# PAGE2-CPU.net
KiCad netlist of a schematic drawn in Altium Designer
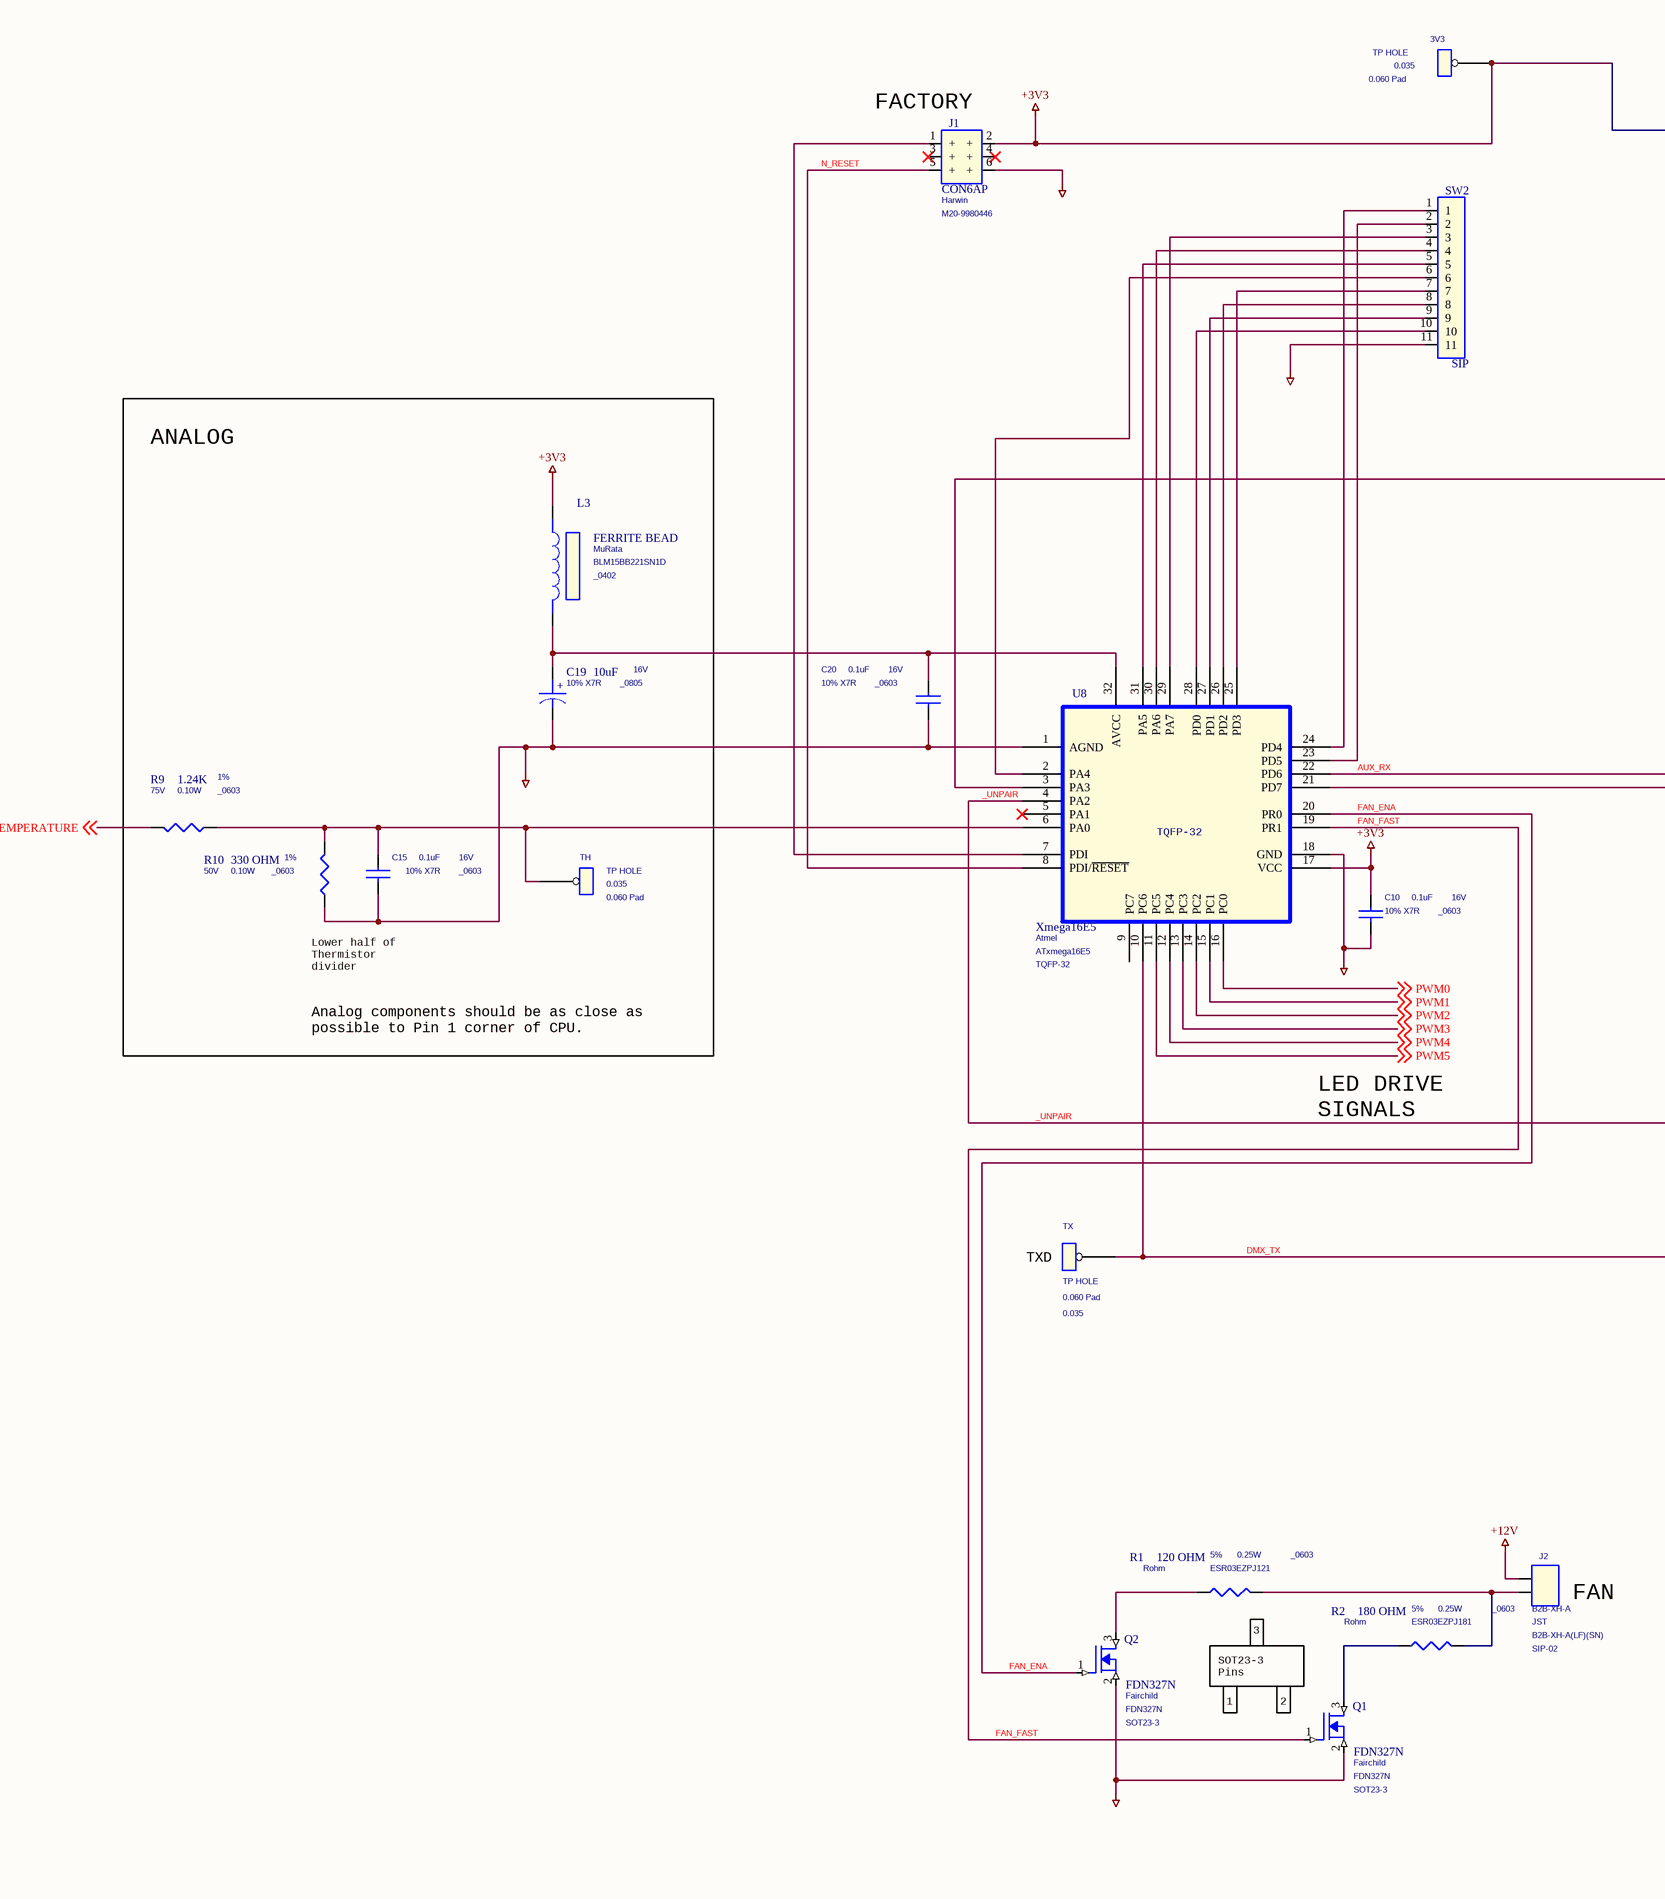
[diagram p0: PAGE2-CPU.SchDoc, left]
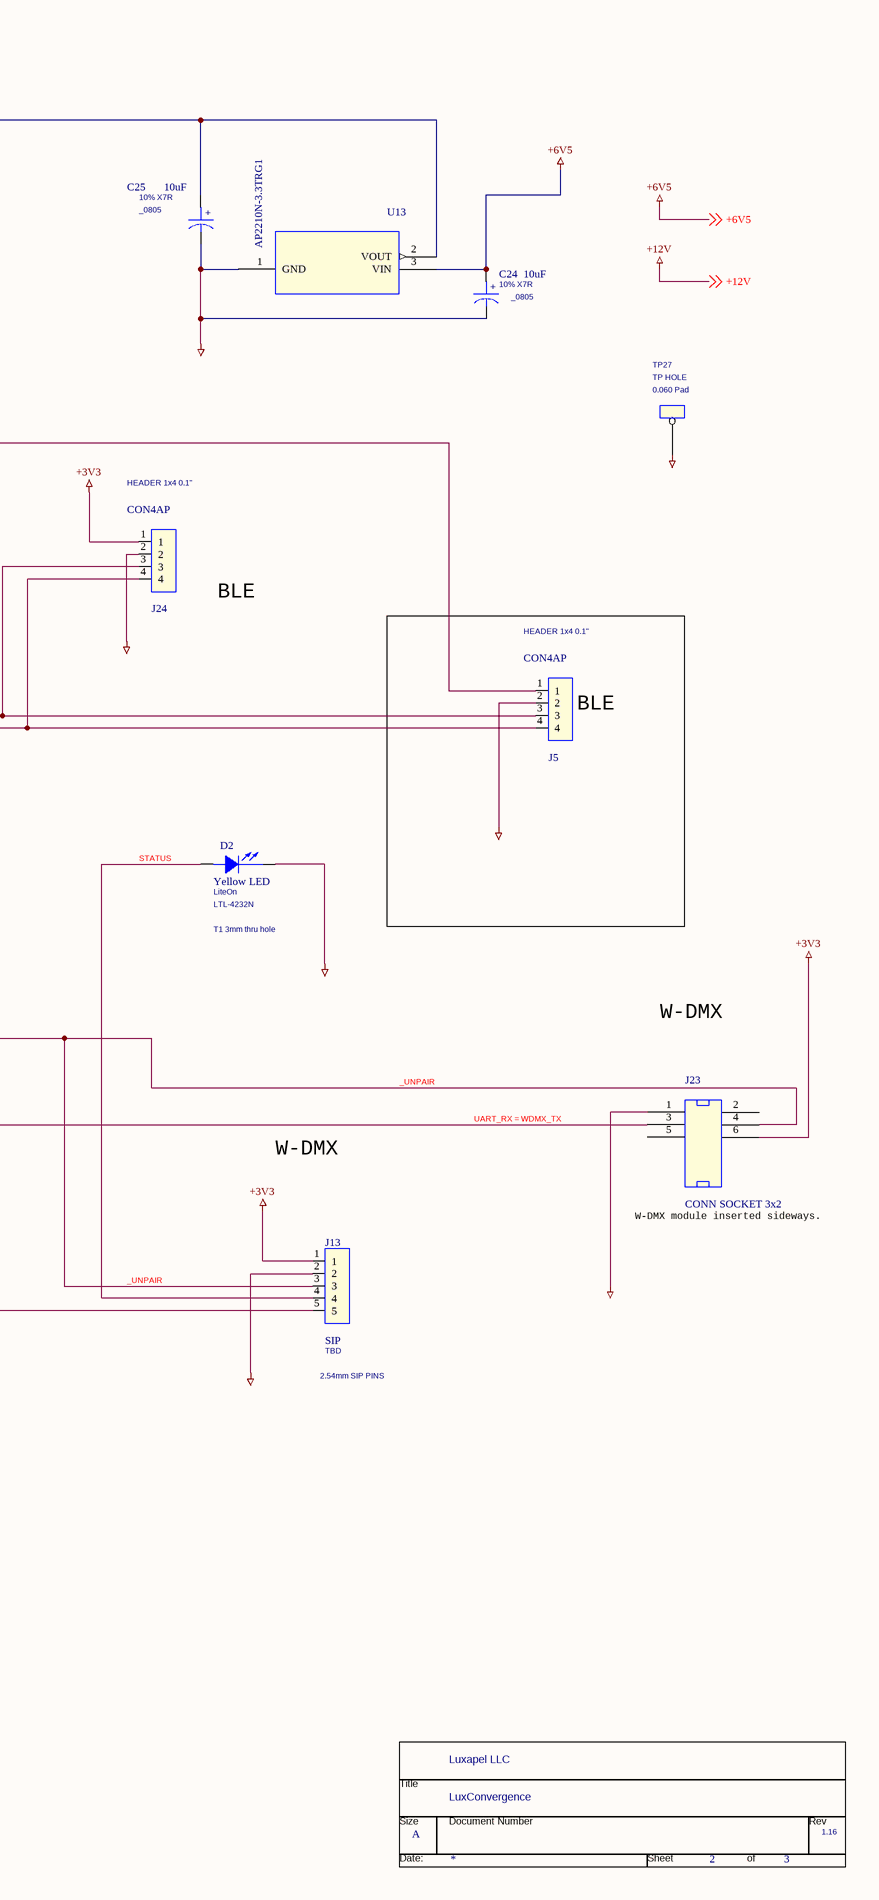
[diagram p1: PAGE2-CPU.SchDoc, right]

(export (version "E")
  (design (tool "Eeschema 10.0.6"))
  (components
    (comp (ref "3V3")
      (value "TP HOLE")
      (footprint "0.035")
      (fields (field (name "NOTES") "0.060 Pad") (field (name "PCB FOOTPRINT") "0.035"))
      (libsource (lib "*") (part "TEST POINT_1"))
    )
    (comp (ref "C10")
      (value "0.1uF")
      (footprint "_0603")
      (fields
        (field (name "PCB FOOTPRINT") "_0603")
        (field (name "VOLTAGE") "16V")
        (field (name "PRECISION") "10% X7R")
        (field (name "MFG") "AVX")
      )
      (libsource (lib "*") (part "CAPACITOR NON-POL"))
    )
    (comp (ref "C15")
      (value "0.1uF")
      (footprint "_0603")
      (fields
        (field (name "PCB FOOTPRINT") "_0603")
        (field (name "MFG") "AVX")
        (field (name "PRECISION") "10% X7R")
        (field (name "VOLTAGE") "16V")
      )
      (libsource (lib "*") (part "CAPACITOR NON-POL"))
    )
    (comp (ref "C19")
      (value "10uF")
      (footprint "_0805")
      (fields
        (field (name "PCB FOOTPRINT") "_0805")
        (field (name "MFG") "Samsung")
        (field (name "VOLTAGE") "16V")
        (field (name "PRECISION") "10% X7R")
      )
      (libsource (lib "*") (part "CAPACITOR POL/SM"))
    )
    (comp (ref "C20")
      (value "0.1uF")
      (footprint "_0603")
      (fields
        (field (name "MFG") "AVX")
        (field (name "PRECISION") "10% X7R")
        (field (name "VOLTAGE") "16V")
        (field (name "PCB FOOTPRINT") "_0603")
      )
      (libsource (lib "*") (part "CAPACITOR NON-POL"))
    )
    (comp (ref "C24")
      (value "10uF")
      (footprint "_0805")
      (fields
        (field (name "PRECISION") "10% X7R")
        (field (name "VOLTAGE") "16V")
        (field (name "MFG") "Samsung")
        (field (name "PCB FOOTPRINT") "_0805")
      )
      (libsource (lib "*") (part "CAPACITOR POL/SM"))
    )
    (comp (ref "C25")
      (value "10uF")
      (footprint "_0805")
      (fields
        (field (name "MFG") "Samsung")
        (field (name "VOLTAGE") "16V")
        (field (name "PRECISION") "10% X7R")
        (field (name "PCB FOOTPRINT") "_0805")
      )
      (libsource (lib "*") (part "CAPACITOR POL/SM"))
    )
    (comp (ref "D2")
      (value "Yellow LED")
      (footprint "T1 3mm thru hole")
      (fields
        (field (name "MFG") "LiteOn")
        (field (name "P/N") "LTL-4232N")
        (field (name "PCB FOOTPRINT") "T1 3mm thru hole")
      )
      (libsource (lib "*") (part "LED"))
    )
    (comp (ref "J1")
      (value "CON6AP")
      (footprint "2x4")
      (fields (field (name "MFG") "Harwin") (field (name "P/N") "M20-9980446"))
      (libsource (lib "*") (part "CON8AP_0"))
    )
    (comp (ref "J2")
      (value "B2B-XH-A")
      (footprint "SIP-02")
      (fields
        (field (name "P/N") "B2B-XH-A(LF)(SN)")
        (field (name "MFG") "JST")
        (field (name "PCB FOOTPRINT") "SIP-02")
      )
      (libsource (lib "*") (part "CON2"))
    )
    (comp (ref "J5")
      (value "CON4AP")
      (footprint "HEADER 1x4 0.1\"")
      (fields (field (name "PCB FOOTPRINT") "HEADER 1x4 0.1\""))
      (libsource (lib "*") (part "CON4AP_5"))
    )
    (comp (ref "J13")
      (value "SIP")
      (footprint "SIP-4")
      (fields (field (name "MFG") "TBD") (field (name "P/N") "2.54mm SIP PINS"))
      (libsource (lib "*") (part "CON4_9"))
    )
    (comp (ref "J23")
      (value "CONN SOCKET 3x2")
      (footprint "2X3")
      (libsource (lib "*") (part "CONN SOCKET 6x2_0"))
    )
    (comp (ref "J24")
      (value "CON4AP")
      (footprint "SIP-4PA")
      (fields (field (name "PCB FOOTPRINT") "HEADER 1x4 0.1\""))
      (libsource (lib "*") (part "CON4AP_5"))
    )
    (comp (ref "L3")
      (value "FERRITE BEAD")
      (footprint "_0402")
      (fields
        (field (name "MFG") "MuRata")
        (field (name "P/N") "BLM15BB221SN1D")
        (field (name "PCB FOOTPRINT") "_0402")
      )
      (libsource (lib "*") (part "INDUCTOR FERRITE/SM"))
    )
    (comp (ref "Q1")
      (value "FDN327N")
      (footprint "SOT23-3")
      (fields
        (field (name "P/N") "FDN327N")
        (field (name "MFG") "Fairchild")
        (field (name "VOLTAGE") "20V")
        (field (name "POWER") "2A")
        (field (name "PCB FOOTPRINT") "SOT23-3")
      )
      (libsource (lib "*") (part "N DGS_0"))
    )
    (comp (ref "Q2")
      (value "FDN327N")
      (footprint "SOT23-3")
      (fields
        (field (name "MFG") "Fairchild")
        (field (name "P/N") "FDN327N")
        (field (name "VOLTAGE") "20V")
        (field (name "POWER") "2A")
        (field (name "PCB FOOTPRINT") "SOT23-3")
      )
      (libsource (lib "*") (part "N DGS_0"))
    )
    (comp (ref "R1")
      (value "120 OHM")
      (footprint "_0603")
      (fields
        (field (name "VOLTAGE") "50V")
        (field (name "PRECISION") "5%")
        (field (name "POWER") "0.25W")
        (field (name "P/N") "ESR03EZPJ121")
        (field (name "MFG") "Rohm")
        (field (name "PCB FOOTPRINT") "_0603")
      )
      (libsource (lib "*") (part "RESISTOR/SM"))
    )
    (comp (ref "R2")
      (value "180 OHM")
      (footprint "_0603")
      (fields
        (field (name "VOLTAGE") "50V")
        (field (name "PRECISION") "5%")
        (field (name "POWER") "0.25W")
        (field (name "P/N") "ESR03EZPJ181")
        (field (name "MFG") "Rohm")
        (field (name "PCB FOOTPRINT") "_0603")
      )
      (libsource (lib "*") (part "RESISTOR/SM"))
    )
    (comp (ref "R9")
      (value "1.24K")
      (footprint "_0603")
      (fields
        (field (name "PCB FOOTPRINT") "_0603")
        (field (name "POWER") "0.10W")
        (field (name "VOLTAGE") "75V")
        (field (name "MFG") "Vishay")
        (field (name "PRECISION") "1%")
      )
      (libsource (lib "*") (part "RESISTOR/SM"))
    )
    (comp (ref "R10")
      (value "330 OHM")
      (footprint "_0603")
      (fields
        (field (name "PCB FOOTPRINT") "_0603")
        (field (name "VOLTAGE") "50V")
        (field (name "PRECISION") "1%")
        (field (name "POWER") "0.10W")
        (field (name "MFG") "Stackpole")
      )
      (libsource (lib "*") (part "RESISTOR/SM"))
    )
    (comp (ref "SW2")
      (value "SIP")
      (footprint "SIP-4")
      (fields (field (name "MFG") "TBD"))
      (libsource (lib "*") (part "CON4_10"))
    )
    (comp (ref "TH")
      (value "TP HOLE")
      (footprint "0.035")
      (fields (field (name "NOTES") "0.060 Pad") (field (name "PCB FOOTPRINT") "0.035"))
      (libsource (lib "") (part "TEST POINT_1_2"))
    )
    (comp (ref "TP27")
      (value "TP HOLE")
      (footprint "0.035")
      (fields (field (name "NOTES") "0.060 Pad"))
      (libsource (lib "") (part "TEST POINT_1_1"))
    )
    (comp (ref "TX")
      (value "TP HOLE")
      (footprint "0.035")
      (fields (field (name "PCB FOOTPRINT") "0.035") (field (name "NOTES") "0.060 Pad"))
      (libsource (lib "*") (part "TEST POINT_1"))
    )
    (comp (ref "U8")
      (value "Xmega16E5")
      (footprint "TQFP-32")
      (fields
        (field (name "P/N") "ATxmega16E5")
        (field (name "MFG") "Atmel")
        (field (name "PCB FOOTPRINT") "TQFP-32")
      )
      (libsource (lib "*") (part "Xmega8E5"))
    )
    (comp (ref "U13")
      (value "AP2210N-3.3TRG1")
      (footprint "FP-SOT23-IPC_A")
      (fields (field (name "COPYRIGHT") "Copyright (C) 2018 Accelerated Designs. All rights reserved"))
      (libsource (lib "*") (part "AP2210N-3P3TRG1"))
    )
  )
  (nets
    (net (code "1") (name "+3V3") (class "Default")
      (node (ref "3V3") (pin "1") (pinfunction "1_1") (pintype "passive"))
      (node (ref "C10") (pin "1") (pinfunction "1_1") (pintype "passive"))
      (node (ref "C25") (pin "1") (pinfunction "1_1") (pintype "passive"))
      (node (ref "J1") (pin "2") (pinfunction "+_2") (pintype "passive"))
      (node (ref "J13") (pin "1") (pinfunction "1_1") (pintype "passive"))
      (node (ref "J23") (pin "6") (pinfunction "9_6") (pintype "passive"))
      (node (ref "J24") (pin "1") (pinfunction "1_1") (pintype "passive"))
      (node (ref "L3") (pin "2") (pinfunction "2_2") (pintype "passive"))
      (node (ref "U13") (pin "2") (pinfunction "VOUT_2") (pintype "output"))
      (node (ref "U8") (pin "17") (pinfunction "VCC_17") (pintype "power_in"))
    )
    (net (code "2") (name "+6V5") (class "Default")
      (node (ref "C24") (pin "1") (pinfunction "1_1") (pintype "passive"))
      (node (ref "U13") (pin "3") (pinfunction "VIN_3") (pintype "passive"))
    )
    (net (code "3") (name "+12V") (class "Default")
      (node (ref "J2") (pin "1") (pinfunction "1_1") (pintype "passive"))
    )
    (net (code "4") (name "/AUX_RX") (class "Default")
      (node (ref "J24") (pin "3") (pinfunction "3_3") (pintype "passive"))
      (node (ref "J5") (pin "3") (pinfunction "3_3") (pintype "passive"))
      (node (ref "U8") (pin "22") (pinfunction "PD6_22") (pintype "passive"))
    )
    (net (code "5") (name "/DMX_TX") (class "Default")
      (node (ref "J13") (pin "5") (pinfunction "5_5") (pintype "passive"))
      (node (ref "J23") (pin "3") (pinfunction "2_3") (pintype "passive"))
      (node (ref "TX") (pin "1") (pinfunction "1_1") (pintype "passive"))
      (node (ref "U8") (pin "10") (pinfunction "PC6_10") (pintype "passive"))
    )
    (net (code "6") (name "/FAN_ENA") (class "Default")
      (node (ref "Q2") (pin "1") (pinfunction "GATE_1") (pintype "input"))
      (node (ref "U8") (pin "20") (pinfunction "PR0_20") (pintype "passive"))
    )
    (net (code "7") (name "/FAN_FAST") (class "Default")
      (node (ref "Q1") (pin "1") (pinfunction "GATE_1") (pintype "input"))
      (node (ref "U8") (pin "19") (pinfunction "PR1_19") (pintype "passive"))
    )
    (net (code "8") (name "/N_RESET") (class "Default")
      (node (ref "J1") (pin "5") (pinfunction "+_5") (pintype "passive"))
      (node (ref "U8") (pin "8") (pinfunction "PDI/~{RESET}_8") (pintype "passive"))
    )
    (net (code "9") (name "/STATUS") (class "Default")
      (node (ref "D2") (pin "1") (pinfunction "ANODE_1") (pintype "passive"))
      (node (ref "J13") (pin "4") (pinfunction "4_4") (pintype "passive"))
    )
    (net (code "10") (name "/_UNPAIR") (class "Default")
      (node (ref "J13") (pin "3") (pinfunction "3_3") (pintype "passive"))
      (node (ref "J23") (pin "4") (pinfunction "8_4") (pintype "passive"))
      (node (ref "U8") (pin "4") (pinfunction "PA2_4") (pintype "passive"))
    )
    (net (code "11") (name "GND_POWER.global") (class "Default")
      (node (ref "C10") (pin "2") (pinfunction "2_2") (pintype "passive"))
      (node (ref "C15") (pin "2") (pinfunction "2_2") (pintype "passive"))
      (node (ref "C19") (pin "2") (pinfunction "2_2") (pintype "passive"))
      (node (ref "C20") (pin "2") (pinfunction "2_2") (pintype "passive"))
      (node (ref "C24") (pin "2") (pinfunction "2_2") (pintype "passive"))
      (node (ref "C25") (pin "2") (pinfunction "2_2") (pintype "passive"))
      (node (ref "D2") (pin "2") (pinfunction "CATHODE_2") (pintype "passive"))
      (node (ref "J1") (pin "6") (pinfunction "+_6") (pintype "passive"))
      (node (ref "J13") (pin "2") (pinfunction "2_2") (pintype "passive"))
      (node (ref "J23") (pin "1") (pinfunction "1_1") (pintype "passive"))
      (node (ref "J24") (pin "2") (pinfunction "2_2") (pintype "passive"))
      (node (ref "J5") (pin "2") (pinfunction "2_2") (pintype "passive"))
      (node (ref "Q1") (pin "2") (pinfunction "SOURCE_2") (pintype "input"))
      (node (ref "Q2") (pin "2") (pinfunction "SOURCE_2") (pintype "input"))
      (node (ref "R10") (pin "2") (pinfunction "2_2") (pintype "passive"))
      (node (ref "SW2") (pin "11") (pinfunction "11_11") (pintype "passive"))
      (node (ref "TP27") (pin "1") (pinfunction "1_1") (pintype "passive"))
      (node (ref "U13") (pin "1") (pinfunction "GND_1") (pintype "power_in"))
      (node (ref "U8") (pin "1") (pinfunction "AGND_1") (pintype "power_in"))
      (node (ref "U8") (pin "18") (pinfunction "GND_18") (pintype "power_in"))
    )
    (net (code "12") (name "Net-(J2-Pad2)") (class "Default")
      (node (ref "J2") (pin "2") (pinfunction "2_2") (pintype "passive"))
      (node (ref "R1") (pin "2") (pinfunction "2_2") (pintype "passive"))
      (node (ref "R2") (pin "2") (pinfunction "2_2") (pintype "passive"))
    )
    (net (code "13") (name "Net-(Q1-DRAIN)") (class "Default")
      (node (ref "Q1") (pin "3") (pinfunction "DRAIN_3") (pintype "input"))
      (node (ref "R2") (pin "1") (pinfunction "1_1") (pintype "passive"))
    )
    (net (code "14") (name "Net-(Q2-DRAIN)") (class "Default")
      (node (ref "Q2") (pin "3") (pinfunction "DRAIN_3") (pintype "input"))
      (node (ref "R1") (pin "1") (pinfunction "1_1") (pintype "passive"))
    )
    (net (code "15") (name "Net-(U8-AVCC)") (class "Default")
      (node (ref "C19") (pin "1") (pinfunction "1_1") (pintype "passive"))
      (node (ref "C20") (pin "1") (pinfunction "1_1") (pintype "passive"))
      (node (ref "L3") (pin "1") (pinfunction "1_1") (pintype "passive"))
      (node (ref "U8") (pin "32") (pinfunction "AVCC_32") (pintype "power_in"))
    )
    (net (code "16") (name "Net-(U8-PA0)") (class "Default")
      (node (ref "C15") (pin "1") (pinfunction "1_1") (pintype "passive"))
      (node (ref "R10") (pin "1") (pinfunction "1_1") (pintype "passive"))
      (node (ref "R9") (pin "2") (pinfunction "2_2") (pintype "passive"))
      (node (ref "TH") (pin "1") (pinfunction "1_1") (pintype "passive"))
      (node (ref "U8") (pin "6") (pinfunction "PA0_6") (pintype "passive"))
    )
    (net (code "17") (name "Net-(U8-PA3)") (class "Default")
      (node (ref "J5") (pin "1") (pinfunction "1_1") (pintype "passive"))
      (node (ref "U8") (pin "3") (pinfunction "PA3_3") (pintype "passive"))
    )
    (net (code "18") (name "Net-(U8-PA4)") (class "Default")
      (node (ref "SW2") (pin "6") (pinfunction "6_6") (pintype "passive"))
      (node (ref "U8") (pin "2") (pinfunction "PA4_2") (pintype "passive"))
    )
    (net (code "19") (name "Net-(U8-PA5)") (class "Default")
      (node (ref "SW2") (pin "5") (pinfunction "5_5") (pintype "passive"))
      (node (ref "U8") (pin "31") (pinfunction "PA5_31") (pintype "passive"))
    )
    (net (code "20") (name "Net-(U8-PA6)") (class "Default")
      (node (ref "SW2") (pin "4") (pinfunction "4_4") (pintype "passive"))
      (node (ref "U8") (pin "30") (pinfunction "PA6_30") (pintype "passive"))
    )
    (net (code "21") (name "Net-(U8-PA7)") (class "Default")
      (node (ref "SW2") (pin "3") (pinfunction "3_3") (pintype "passive"))
      (node (ref "U8") (pin "29") (pinfunction "PA7_29") (pintype "passive"))
    )
    (net (code "22") (name "Net-(U8-PD0)") (class "Default")
      (node (ref "SW2") (pin "10") (pinfunction "10_10") (pintype "passive"))
      (node (ref "U8") (pin "28") (pinfunction "PD0_28") (pintype "passive"))
    )
    (net (code "23") (name "Net-(U8-PD1)") (class "Default")
      (node (ref "SW2") (pin "9") (pinfunction "9_9") (pintype "passive"))
      (node (ref "U8") (pin "27") (pinfunction "PD1_27") (pintype "passive"))
    )
    (net (code "24") (name "Net-(U8-PD2)") (class "Default")
      (node (ref "SW2") (pin "8") (pinfunction "8_8") (pintype "passive"))
      (node (ref "U8") (pin "26") (pinfunction "PD2_26") (pintype "passive"))
    )
    (net (code "25") (name "Net-(U8-PD3)") (class "Default")
      (node (ref "SW2") (pin "7") (pinfunction "7_7") (pintype "passive"))
      (node (ref "U8") (pin "25") (pinfunction "PD3_25") (pintype "passive"))
    )
    (net (code "26") (name "Net-(U8-PD4)") (class "Default")
      (node (ref "SW2") (pin "1") (pinfunction "1_1") (pintype "passive"))
      (node (ref "U8") (pin "24") (pinfunction "PD4_24") (pintype "passive"))
    )
    (net (code "27") (name "Net-(U8-PD5)") (class "Default")
      (node (ref "SW2") (pin "2") (pinfunction "2_2") (pintype "passive"))
      (node (ref "U8") (pin "23") (pinfunction "PD5_23") (pintype "passive"))
    )
    (net (code "28") (name "Net-(U8-PD7)") (class "Default")
      (node (ref "J24") (pin "4") (pinfunction "4_4") (pintype "passive"))
      (node (ref "J5") (pin "4") (pinfunction "4_4") (pintype "passive"))
      (node (ref "U8") (pin "21") (pinfunction "PD7_21") (pintype "passive"))
    )
    (net (code "29") (name "Net-(U8-PDI)") (class "Default")
      (node (ref "J1") (pin "1") (pinfunction "+_1") (pintype "passive"))
      (node (ref "U8") (pin "7") (pinfunction "PDI_7") (pintype "passive"))
    )
    (net (code "30") (name "PWM0") (class "Default")
      (node (ref "U8") (pin "16") (pinfunction "PC0_16") (pintype "passive"))
    )
    (net (code "31") (name "PWM1") (class "Default")
      (node (ref "U8") (pin "15") (pinfunction "PC1_15") (pintype "passive"))
    )
    (net (code "32") (name "PWM2") (class "Default")
      (node (ref "U8") (pin "14") (pinfunction "PC2_14") (pintype "passive"))
    )
    (net (code "33") (name "PWM3") (class "Default")
      (node (ref "U8") (pin "13") (pinfunction "PC3_13") (pintype "passive"))
    )
    (net (code "34") (name "PWM4") (class "Default")
      (node (ref "U8") (pin "12") (pinfunction "PC4_12") (pintype "passive"))
    )
    (net (code "35") (name "PWM5") (class "Default")
      (node (ref "U8") (pin "11") (pinfunction "PC5_11") (pintype "passive"))
    )
    (net (code "36") (name "TEMPERATURE") (class "Default")
      (node (ref "R9") (pin "1") (pinfunction "1_1") (pintype "passive"))
    )
    (net (code "37") (name "unconnected-(J1-+-Pad3)") (class "Default")
      (node (ref "J1") (pin "3") (pinfunction "+_3") (pintype "passive+no_connect"))
    )
    (net (code "38") (name "unconnected-(J1-+-Pad4)") (class "Default")
      (node (ref "J1") (pin "4") (pinfunction "+_4") (pintype "passive+no_connect"))
    )
    (net (code "39") (name "unconnected-(J23-3-Pad5)") (class "Default")
      (node (ref "J23") (pin "5") (pinfunction "3_5") (pintype "passive"))
    )
    (net (code "40") (name "unconnected-(J23-7-Pad2)") (class "Default")
      (node (ref "J23") (pin "2") (pinfunction "7_2") (pintype "passive"))
    )
    (net (code "41") (name "unconnected-(U8-PA1-Pad5)") (class "Default")
      (node (ref "U8") (pin "5") (pinfunction "PA1_5") (pintype "passive+no_connect"))
    )
    (net (code "42") (name "unconnected-(U8-PC7-Pad9)") (class "Default")
      (node (ref "U8") (pin "9") (pinfunction "PC7_9") (pintype "passive"))
    )
  )
)
